# Sheet1.net
KiCad netlist of a schematic drawn in Altium Designer
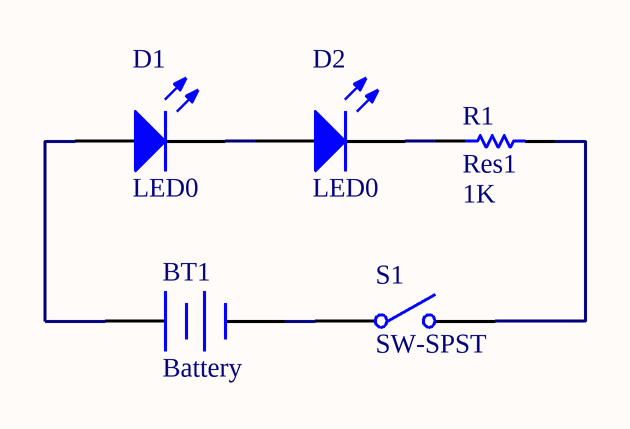
[diagram p0: Sheet1.SchDoc]

(export (version "E")
  (design (tool "Eeschema 10.0.6"))
  (components
    (comp (ref "BT1")
      (value "Battery")
      (footprint "BAT-2")
      (description "Multicell Battery")
      (fields (field (name "PUBLISHER") "Altium Limited"))
      (libsource (lib "Miscellaneous Devices") (part "Battery"))
    )
    (comp (ref "D1")
      (value "LED0")
      (footprint "LED-0")
      (description "Typical INFRARED GaAs LED")
      (fields (field (name "PUBLISHER") "Altium Limited"))
      (libsource (lib "Miscellaneous Devices") (part "LED0"))
    )
    (comp (ref "D2")
      (value "LED0")
      (footprint "LED-0")
      (description "Typical INFRARED GaAs LED")
      (fields (field (name "PUBLISHER") "Altium Limited"))
      (libsource (lib "Miscellaneous Devices") (part "LED0"))
    )
    (comp (ref "R1")
      (value "Res1")
      (footprint "AXIAL-0.3")
      (description "Resistor")
      (fields (field (name "ALTIUM_VALUE") "1K") (field (name "PUBLISHER") "Altium Limited"))
      (libsource (lib "Miscellaneous Devices") (part "Res1"))
    )
    (comp (ref "S1")
      (value "SW-SPST")
      (footprint "SPST-2")
      (description "Single-Pole, Single-Throw Switch")
      (fields (field (name "PUBLISHER") "Altium Limited"))
      (libsource (lib "Miscellaneous Devices") (part "SW-SPST"))
    )
  )
  (nets
    (net (code "1") (name "Net-(BT1-+)") (class "Default")
      (node (ref "BT1") (pin "1") (pinfunction "+_1") (pintype "passive"))
      (node (ref "D1") (pin "1") (pinfunction "A_1") (pintype "passive"))
    )
    (net (code "2") (name "Net-(BT1--)") (class "Default")
      (node (ref "BT1") (pin "2") (pinfunction "-_2") (pintype "passive"))
      (node (ref "S1") (pin "1") (pinfunction "COMMON_1") (pintype "passive"))
    )
    (net (code "3") (name "Net-(D1-K)") (class "Default")
      (node (ref "D1") (pin "2") (pinfunction "K_2") (pintype "passive"))
      (node (ref "D2") (pin "1") (pinfunction "A_1") (pintype "passive"))
    )
    (net (code "4") (name "Net-(D2-K)") (class "Default")
      (node (ref "D2") (pin "2") (pinfunction "K_2") (pintype "passive"))
      (node (ref "R1") (pin "1") (pinfunction "1_1") (pintype "passive"))
    )
    (net (code "5") (name "Net-(S1-NO)") (class "Default")
      (node (ref "R1") (pin "2") (pinfunction "2_2") (pintype "passive"))
      (node (ref "S1") (pin "2") (pinfunction "NO_2") (pintype "passive"))
    )
  )
)
